# V1_0.net
KiCad netlist of a schematic drawn in Altium Designer
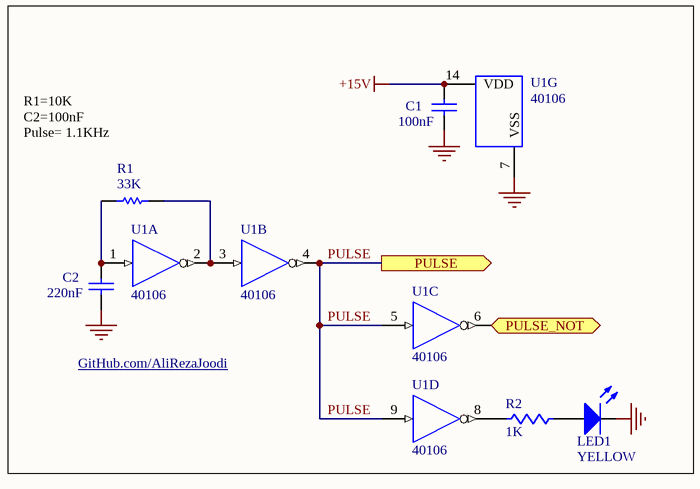
[diagram p0: V1.0.SchDoc]

(export (version "E")
  (design (tool "Eeschema 10.0.6"))
  (components
    (comp (ref "C1")
      (value "100nF")
      (footprint "CAPNTO2.54-3.05x1.78A")
      (description "Capacitor")
      (fields (field (name "MANUFACTURER") "Generic Components") (field (name "PUBLISHER") "Altium Limited"))
      (libsource (lib "Miscellaneous Devices") (part "Cap"))
    )
    (comp (ref "C2")
      (value "220nF")
      (footprint "CAPNTO5.08-7.37x3.94")
      (description "Capacitor")
      (fields (field (name "PUBLISHER") "Altium Limited"))
      (libsource (lib "Miscellaneous Devices") (part "Cap"))
    )
    (comp (ref "LED1")
      (value "YELLOW")
      (footprint "LED-5mm_Red")
      (description "Typical INFRARED GaAs LED")
      (fields (field (name "MANUFACTURER") "Generic Components") (field (name "PUBLISHER") "Altium Limited"))
      (libsource (lib "Miscellaneous Devices") (part "LED"))
    )
    (comp (ref "R1")
      (value "33K")
      (footprint "AXIAL-0.4")
      (description "Resistor")
      (fields (field (name "PUBLISHER") "Altium Limited"))
      (libsource (lib "Miscellaneous Devices") (part "Res1"))
    )
    (comp (ref "R2")
      (value "1K")
      (footprint "AXIAL-0.4")
      (description "Resistor")
      (fields (field (name "MANUFACTURER") "Generic Components") (field (name "PUBLISHER") "Altium Limited"))
      (libsource (lib "") (part "Res1_1"))
    )
    (comp (ref "U1")
      (value "40106")
      (footprint "DIP14")
      (description "Hex inverting Schmitt trigger, 14-Pin")
      (fields (field (name "PUBLISHER") "Altium Limited"))
      (libsource (lib "my Libraries") (part "40106"))
    )
  )
  (nets
    (net (code "1") (name "+15V") (class "Default")
      (node (ref "C1") (pin "2") (pinfunction "2_2") (pintype "passive"))
      (node (ref "U1") (pin "14") (pinfunction "VDD_14") (pintype "passive"))
    )
    (net (code "2") (name "/PULSE") (class "Default")
      (node (ref "U1") (pin "4") (pinfunction "~{O}_4") (pintype "output"))
      (node (ref "U1") (pin "5") (pinfunction "I_5") (pintype "input"))
      (node (ref "U1") (pin "9") (pinfunction "I_9") (pintype "input"))
    )
    (net (code "3") (name "/PULSE_NOT") (class "Default")
      (node (ref "U1") (pin "6") (pinfunction "~{O}_6") (pintype "output"))
    )
    (net (code "4") (name "GND") (class "Default")
      (node (ref "C1") (pin "1") (pinfunction "1_1") (pintype "passive"))
      (node (ref "C2") (pin "1") (pinfunction "1_1") (pintype "passive"))
      (node (ref "LED1") (pin "2") (pinfunction "K_2") (pintype "passive"))
      (node (ref "U1") (pin "7") (pinfunction "VSS_7") (pintype "power_in"))
    )
    (net (code "5") (name "Net-(LED1-A)") (class "Default")
      (node (ref "LED1") (pin "1") (pinfunction "A_1") (pintype "passive"))
      (node (ref "R2") (pin "2") (pinfunction "2_2") (pintype "passive"))
    )
    (net (code "6") (name "Net-(U1A-I)") (class "Default")
      (node (ref "C2") (pin "2") (pinfunction "2_2") (pintype "passive"))
      (node (ref "R1") (pin "2") (pinfunction "2_2") (pintype "passive"))
      (node (ref "U1") (pin "1") (pinfunction "I_1") (pintype "input"))
    )
    (net (code "7") (name "Net-(U1A-~{O})") (class "Default")
      (node (ref "R1") (pin "1") (pinfunction "1_1") (pintype "passive"))
      (node (ref "U1") (pin "2") (pinfunction "~{O}_2") (pintype "output"))
      (node (ref "U1") (pin "3") (pinfunction "I_3") (pintype "input"))
    )
    (net (code "8") (name "Net-(U1D-~{O})") (class "Default")
      (node (ref "R2") (pin "1") (pinfunction "1_1") (pintype "passive"))
      (node (ref "U1") (pin "8") (pinfunction "~{O}_8") (pintype "output"))
    )
  )
)
